# 030Card.net
KiCad netlist of a schematic drawn in EAGLE
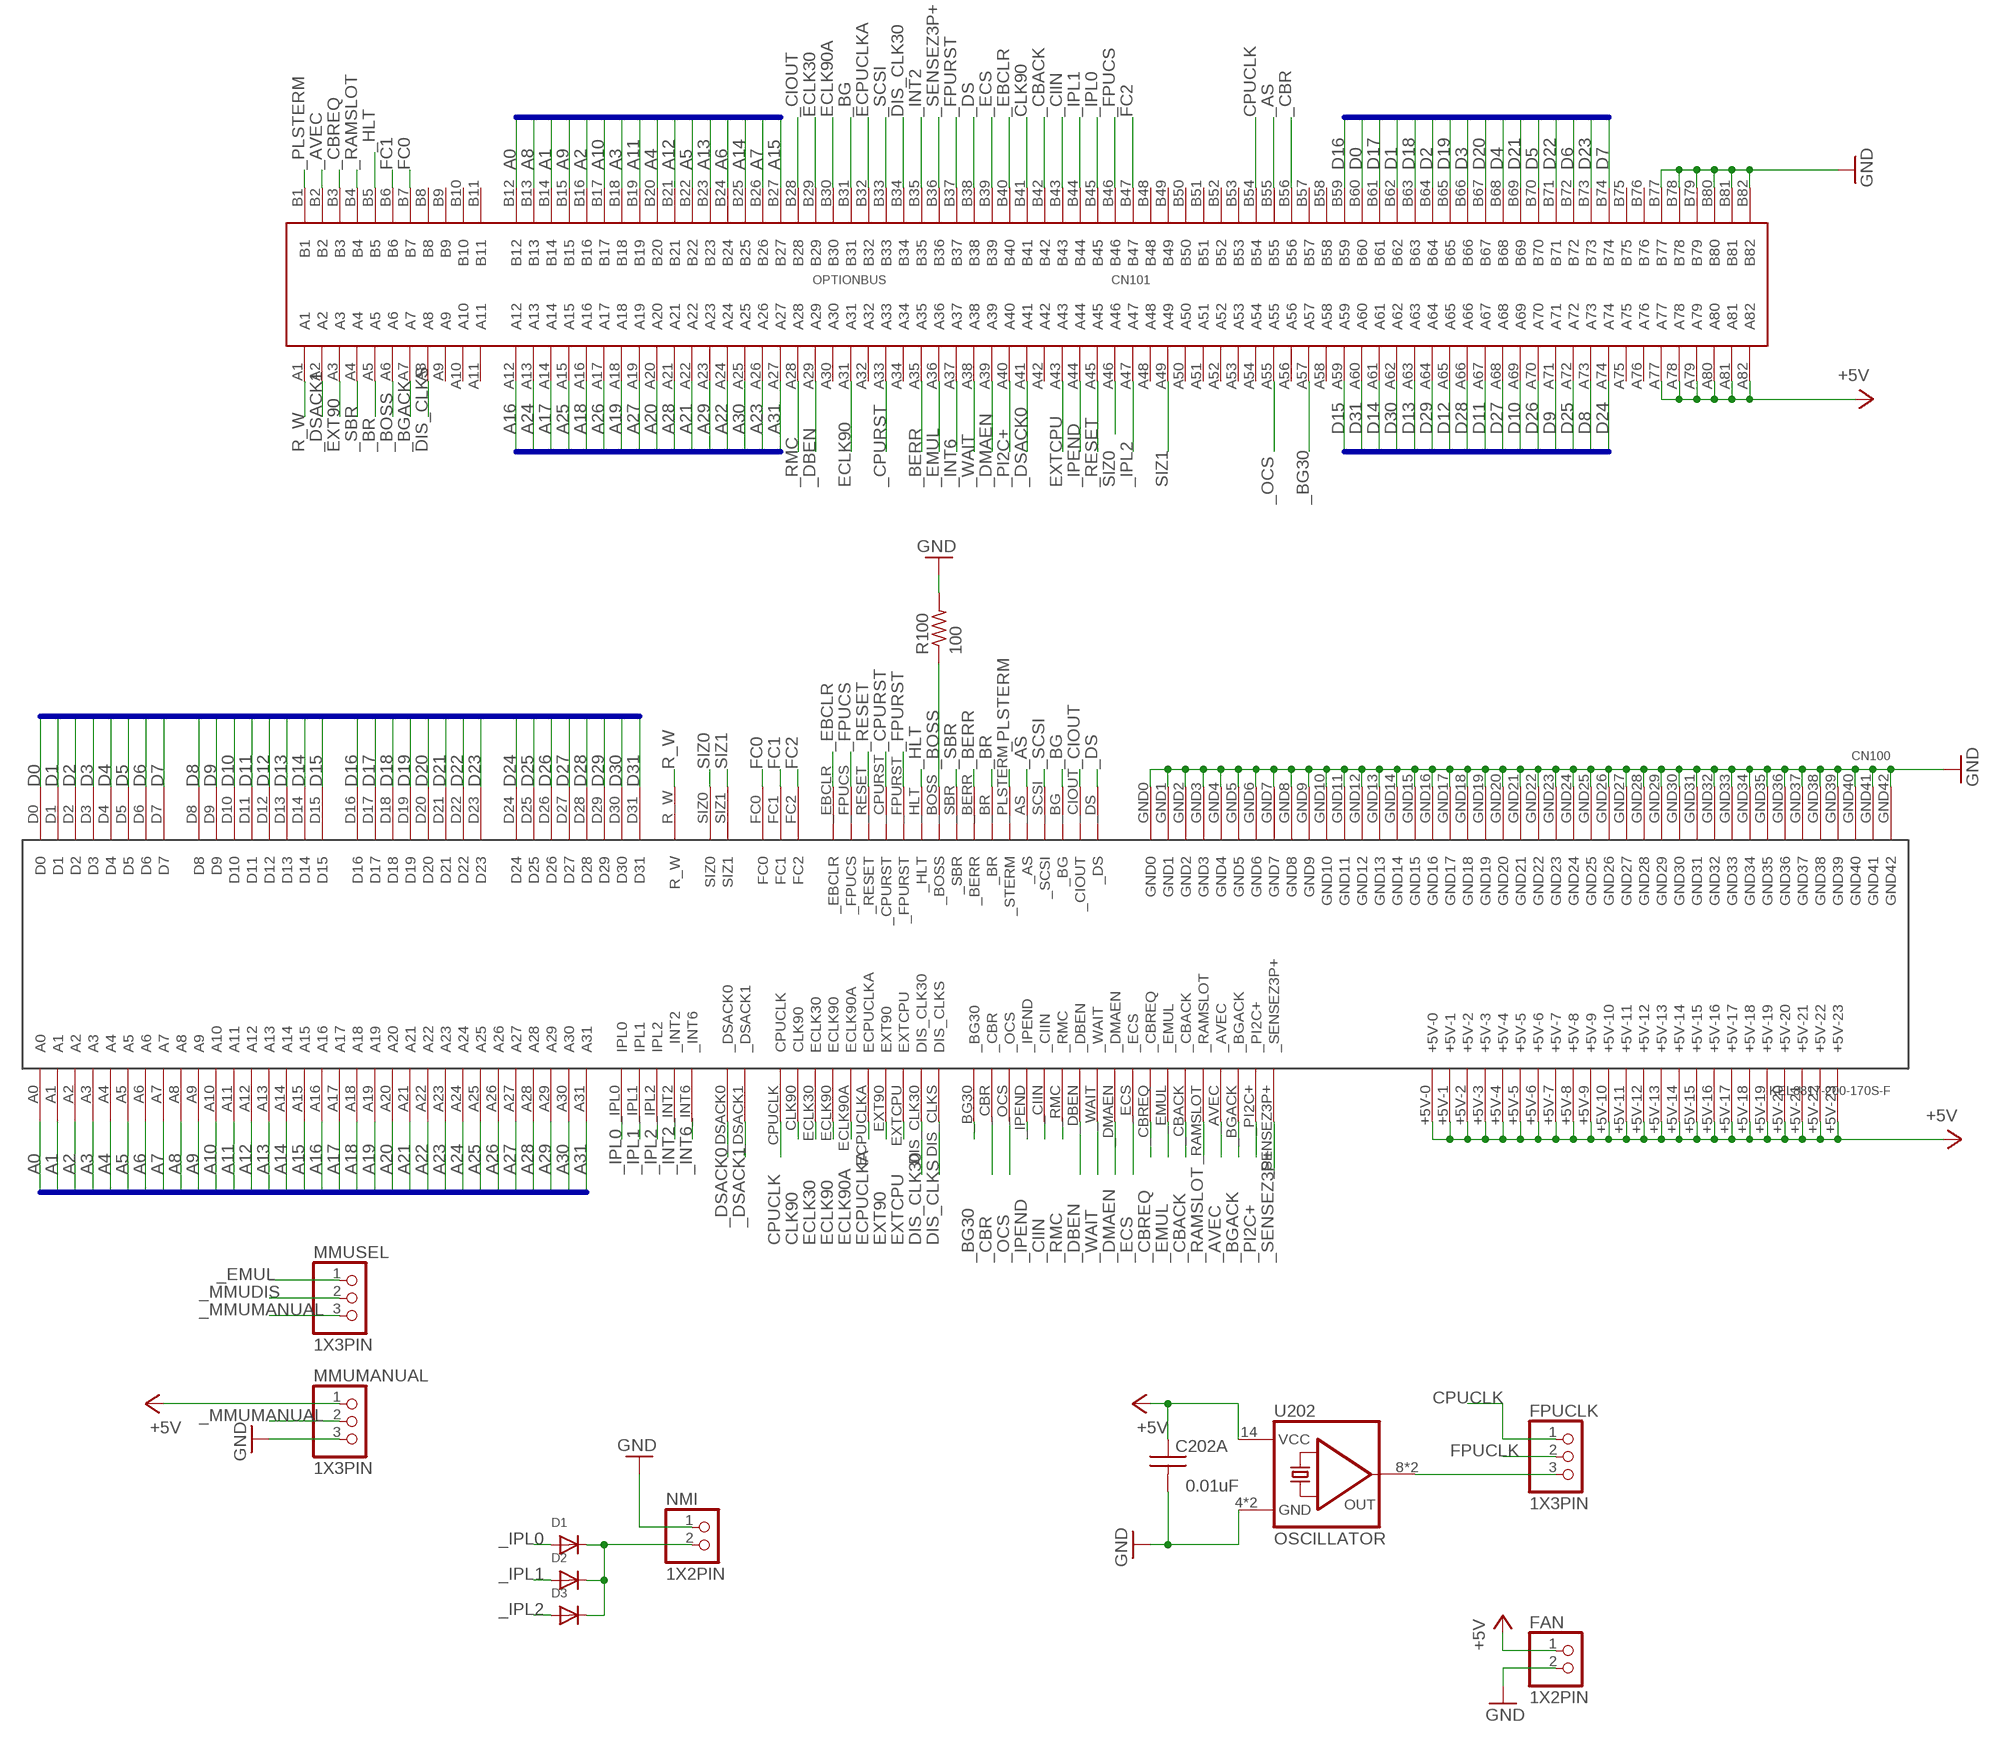
[diagram p0: schematic, sheet 1, part 1 of 2]
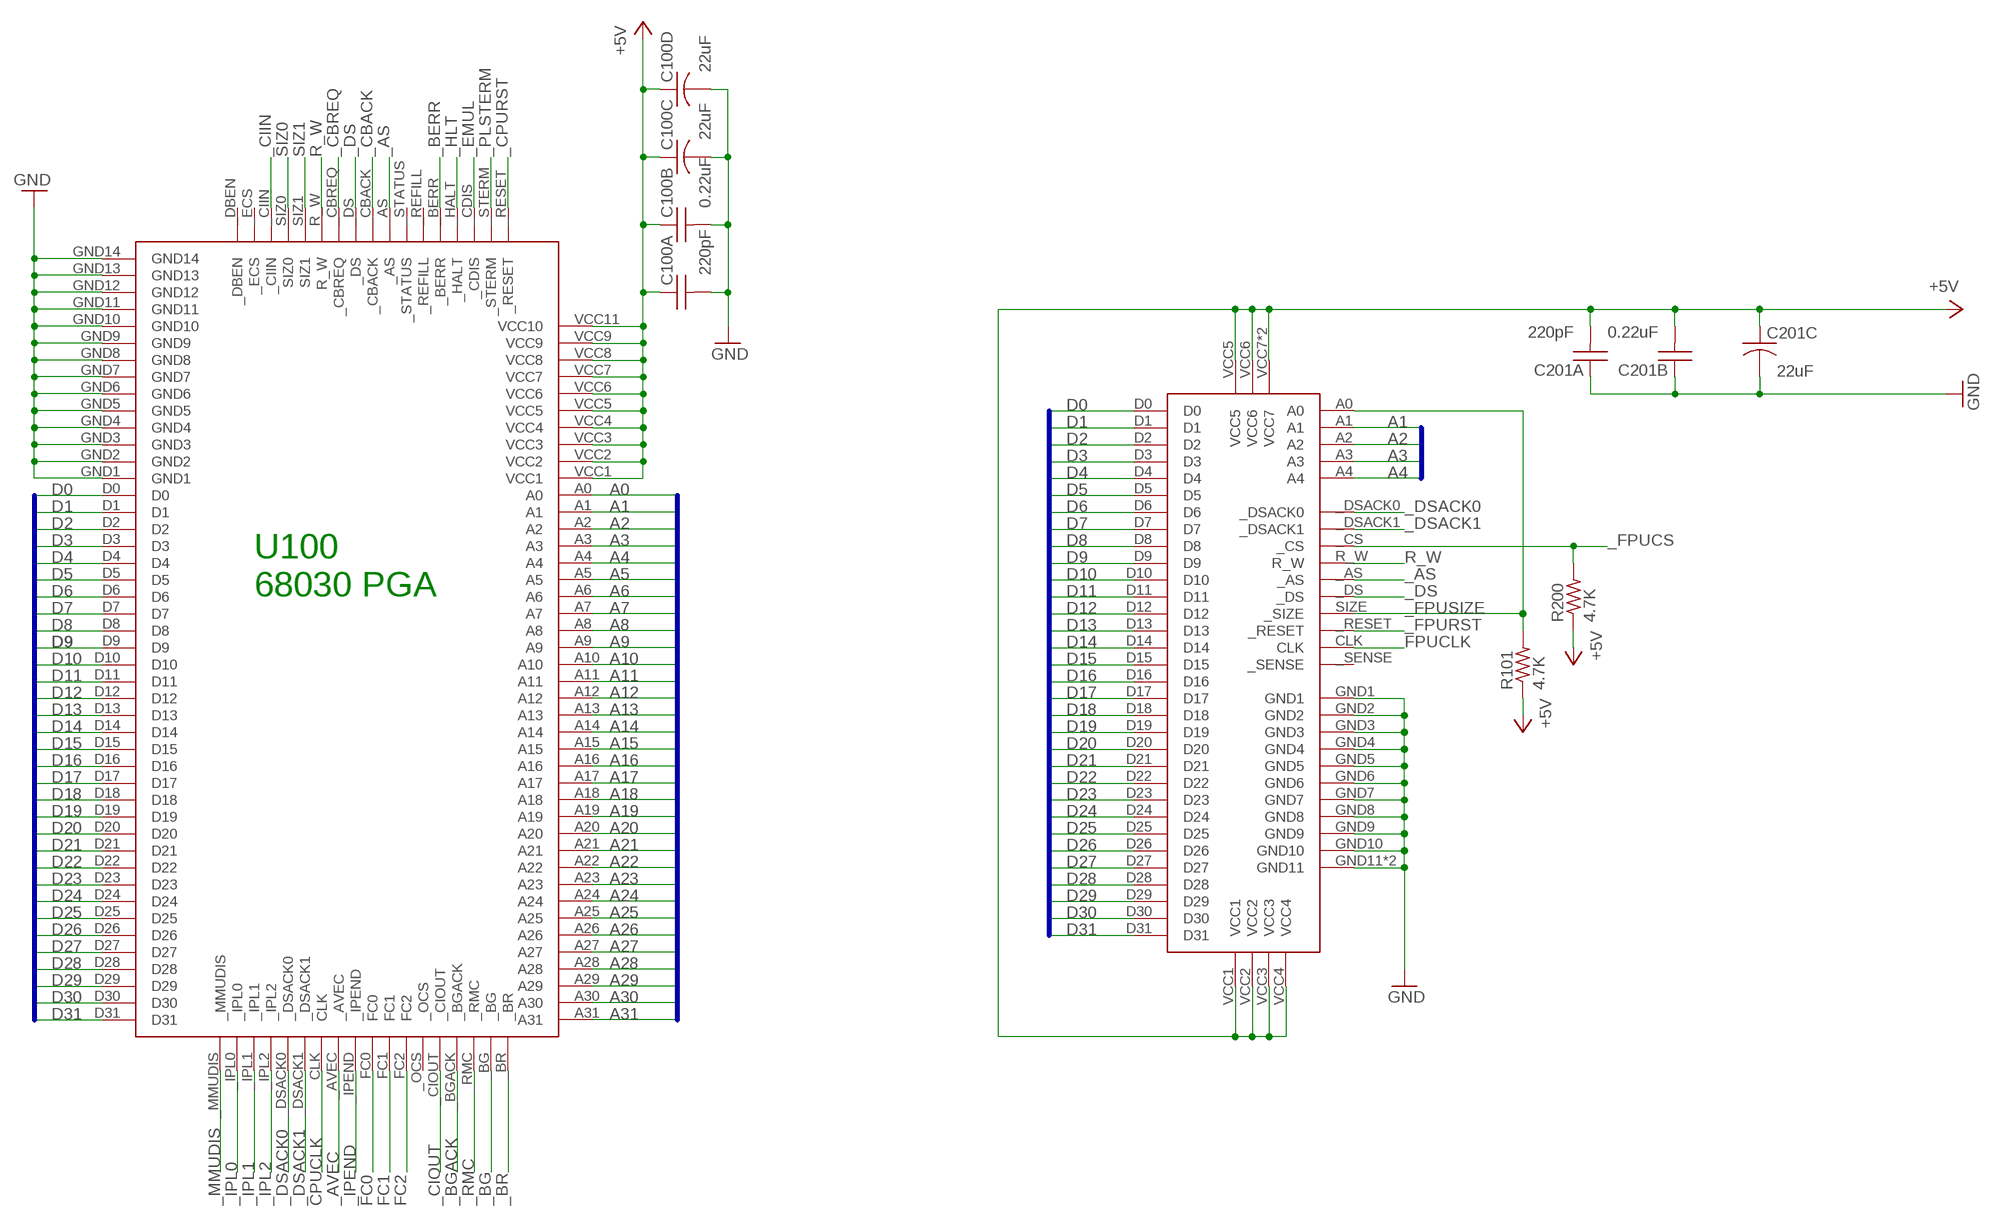
[diagram p1: schematic, sheet 1, part 2 of 2]

(export (version "E")
  (design (tool "Eeschema 10.0.6"))
  (components
    (comp (ref "C100A")
      (value "220pF")
      (footprint "eagle-import:R0805")
      (libsource (lib "eagle-import") (part "C0805"))
    )
    (comp (ref "C100B")
      (value "0.22uF")
      (footprint "eagle-import:R0805")
      (libsource (lib "eagle-import") (part "C0805"))
    )
    (comp (ref "C100C")
      (value "22uF")
      (footprint "eagle-import:SMD-ELECTROLYTE")
      (libsource (lib "eagle-import") (part "SMD-ELECTROLYTE"))
    )
    (comp (ref "C100D")
      (value "22uF")
      (footprint "eagle-import:SMD-ELECTROLYTE")
      (libsource (lib "eagle-import") (part "SMD-ELECTROLYTE"))
    )
    (comp (ref "C201A")
      (value "220pF")
      (footprint "eagle-import:R0805")
      (libsource (lib "eagle-import") (part "C0805"))
    )
    (comp (ref "C201B")
      (value "0.22uF")
      (footprint "eagle-import:R0805")
      (libsource (lib "eagle-import") (part "C0805"))
    )
    (comp (ref "C201C")
      (value "22uF")
      (footprint "eagle-import:SMD-ELECTROLYTE")
      (libsource (lib "eagle-import") (part "SMD-ELECTROLYTE"))
    )
    (comp (ref "C202A")
      (value "0.01uF")
      (footprint "eagle-import:R0805")
      (libsource (lib "eagle-import") (part "C0805"))
    )
    (comp (ref "CN100")
      (value "KEL8817-200-170S-F")
      (footprint "eagle-import:KEL8817-200-170S-F")
      (libsource (lib "eagle-import") (part "KEL8817-200-170S-F"))
    )
    (comp (ref "CN101")
      (value "OPTIONBUS")
      (footprint "eagle-import:OPTIONBUS")
      (libsource (lib "eagle-import") (part "OPTIONBUS"))
    )
    (comp (ref "D1")
      (value "DIODESOD-323F")
      (footprint "eagle-import:SOD-323F")
      (libsource (lib "eagle-import") (part "DIODESOD-323F"))
    )
    (comp (ref "D2")
      (value "DIODESOD-323F")
      (footprint "eagle-import:SOD-323F")
      (libsource (lib "eagle-import") (part "DIODESOD-323F"))
    )
    (comp (ref "D3")
      (value "DIODESOD-323F")
      (footprint "eagle-import:SOD-323F")
      (libsource (lib "eagle-import") (part "DIODESOD-323F"))
    )
    (comp (ref "FAN")
      (value "1X2PIN")
      (footprint "eagle-import:1X2PIN")
      (libsource (lib "eagle-import") (part "1X2PIN"))
    )
    (comp (ref "FPUCLK")
      (value "1X3PIN")
      (footprint "eagle-import:1X3PIN")
      (libsource (lib "eagle-import") (part "1X3PIN"))
    )
    (comp (ref "MMUMANUAL")
      (value "1X3PIN")
      (footprint "eagle-import:1X3PIN")
      (libsource (lib "eagle-import") (part "1X3PIN"))
    )
    (comp (ref "MMUSEL")
      (value "1X3PIN")
      (footprint "eagle-import:1X3PIN")
      (libsource (lib "eagle-import") (part "1X3PIN"))
    )
    (comp (ref "NMI")
      (value "1X2PIN")
      (footprint "eagle-import:1X2PIN")
      (libsource (lib "eagle-import") (part "1X2PIN"))
    )
    (comp (ref "R100")
      (value "100")
      (footprint "eagle-import:R0805")
      (libsource (lib "eagle-import") (part "R-US_R0805"))
    )
    (comp (ref "R101")
      (value "4.7K")
      (footprint "eagle-import:R0805")
      (libsource (lib "eagle-import") (part "R-US_R0805"))
    )
    (comp (ref "R200")
      (value "4.7K")
      (footprint "eagle-import:R0805")
      (libsource (lib "eagle-import") (part "R-US_R0805"))
    )
    (comp (ref "U100")
      (value "M68030")
      (footprint "eagle-import:M68030")
      (libsource (lib "eagle-import") (part "M68030"))
    )
    (comp (ref "U201")
      (value "M68882PLCC")
      (footprint "eagle-import:M68882PLCC")
      (libsource (lib "eagle-import") (part "M68882PLCC"))
    )
    (comp (ref "U202")
      (value "OSCILLATOR")
      (footprint "eagle-import:OSCILLATOR")
      (libsource (lib "eagle-import") (part "OSCILLATOR"))
    )
  )
  (nets
    (net (code "1") (name "+5V") (class "Default")
      (node (ref "C100A") (pin "1") (pinfunction "1_1") (pintype "passive"))
      (node (ref "C100B") (pin "1") (pinfunction "1_1") (pintype "passive"))
      (node (ref "C100C") (pin "+") (pinfunction "1_+") (pintype "passive"))
      (node (ref "C100D") (pin "+") (pinfunction "1_+") (pintype "passive"))
      (node (ref "C201A") (pin "2") (pinfunction "2_2") (pintype "passive"))
      (node (ref "C201B") (pin "2") (pinfunction "2_2") (pintype "passive"))
      (node (ref "C201C") (pin "+") (pinfunction "1_+") (pintype "passive"))
      (node (ref "C202A") (pin "1") (pinfunction "1_1") (pintype "passive"))
      (node (ref "CN100") (pin "+5V-0") (pinfunction "+5V-0_+5V-0") (pintype "bidirectional"))
      (node (ref "CN100") (pin "+5V-1") (pinfunction "+5V-1_+5V-1") (pintype "bidirectional"))
      (node (ref "CN100") (pin "+5V-10") (pinfunction "+5V-10_+5V-10") (pintype "bidirectional"))
      (node (ref "CN100") (pin "+5V-11") (pinfunction "+5V-11_+5V-11") (pintype "bidirectional"))
      (node (ref "CN100") (pin "+5V-12") (pinfunction "+5V-12_+5V-12") (pintype "bidirectional"))
      (node (ref "CN100") (pin "+5V-13") (pinfunction "+5V-13_+5V-13") (pintype "bidirectional"))
      (node (ref "CN100") (pin "+5V-14") (pinfunction "+5V-14_+5V-14") (pintype "bidirectional"))
      (node (ref "CN100") (pin "+5V-15") (pinfunction "+5V-15_+5V-15") (pintype "bidirectional"))
      (node (ref "CN100") (pin "+5V-16") (pinfunction "+5V-16_+5V-16") (pintype "bidirectional"))
      (node (ref "CN100") (pin "+5V-17") (pinfunction "+5V-17_+5V-17") (pintype "bidirectional"))
      (node (ref "CN100") (pin "+5V-18") (pinfunction "+5V-18_+5V-18") (pintype "bidirectional"))
      (node (ref "CN100") (pin "+5V-19") (pinfunction "+5V-19_+5V-19") (pintype "bidirectional"))
      (node (ref "CN100") (pin "+5V-2") (pinfunction "+5V-2_+5V-2") (pintype "bidirectional"))
      (node (ref "CN100") (pin "+5V-20") (pinfunction "+5V-20_+5V-20") (pintype "bidirectional"))
      (node (ref "CN100") (pin "+5V-21") (pinfunction "+5V-21_+5V-21") (pintype "bidirectional"))
      (node (ref "CN100") (pin "+5V-22") (pinfunction "+5V-22_+5V-22") (pintype "bidirectional"))
      (node (ref "CN100") (pin "+5V-23") (pinfunction "+5V-23_+5V-23") (pintype "bidirectional"))
      (node (ref "CN100") (pin "+5V-3") (pinfunction "+5V-3_+5V-3") (pintype "bidirectional"))
      (node (ref "CN100") (pin "+5V-4") (pinfunction "+5V-4_+5V-4") (pintype "bidirectional"))
      (node (ref "CN100") (pin "+5V-5") (pinfunction "+5V-5_+5V-5") (pintype "bidirectional"))
      (node (ref "CN100") (pin "+5V-6") (pinfunction "+5V-6_+5V-6") (pintype "bidirectional"))
      (node (ref "CN100") (pin "+5V-7") (pinfunction "+5V-7_+5V-7") (pintype "bidirectional"))
      (node (ref "CN100") (pin "+5V-8") (pinfunction "+5V-8_+5V-8") (pintype "bidirectional"))
      (node (ref "CN100") (pin "+5V-9") (pinfunction "+5V-9_+5V-9") (pintype "bidirectional"))
      (node (ref "CN101") (pin "A77") (pinfunction "A77_A77") (pintype "bidirectional"))
      (node (ref "CN101") (pin "A78") (pinfunction "A78_A78") (pintype "bidirectional"))
      (node (ref "CN101") (pin "A79") (pinfunction "A79_A79") (pintype "bidirectional"))
      (node (ref "CN101") (pin "A80") (pinfunction "A80_A80") (pintype "bidirectional"))
      (node (ref "CN101") (pin "A81") (pinfunction "A81_A81") (pintype "bidirectional"))
      (node (ref "CN101") (pin "A82") (pinfunction "A82_A82") (pintype "bidirectional"))
      (node (ref "FAN") (pin "1") (pinfunction "1_1") (pintype "passive"))
      (node (ref "MMUMANUAL") (pin "1") (pinfunction "1_1") (pintype "passive"))
      (node (ref "R101") (pin "1") (pinfunction "1_1") (pintype "passive"))
      (node (ref "R200") (pin "1") (pinfunction "1_1") (pintype "passive"))
      (node (ref "U100") (pin "VCC1") (pinfunction "VCC1_VCC1") (pintype "bidirectional"))
      (node (ref "U100") (pin "VCC11") (pinfunction "VCC10_VCC11") (pintype "bidirectional"))
      (node (ref "U100") (pin "VCC2") (pinfunction "VCC2_VCC2") (pintype "bidirectional"))
      (node (ref "U100") (pin "VCC3") (pinfunction "VCC3_VCC3") (pintype "bidirectional"))
      (node (ref "U100") (pin "VCC4") (pinfunction "VCC4_VCC4") (pintype "bidirectional"))
      (node (ref "U100") (pin "VCC5") (pinfunction "VCC5_VCC5") (pintype "bidirectional"))
      (node (ref "U100") (pin "VCC6") (pinfunction "VCC6_VCC6") (pintype "bidirectional"))
      (node (ref "U100") (pin "VCC7") (pinfunction "VCC7_VCC7") (pintype "bidirectional"))
      (node (ref "U100") (pin "VCC8") (pinfunction "VCC8_VCC8") (pintype "bidirectional"))
      (node (ref "U100") (pin "VCC9") (pinfunction "VCC9_VCC9") (pintype "bidirectional"))
      (node (ref "U201") (pin "VCC1") (pinfunction "VCC1_VCC1") (pintype "bidirectional"))
      (node (ref "U201") (pin "VCC2") (pinfunction "VCC2_VCC2") (pintype "bidirectional"))
      (node (ref "U201") (pin "VCC3") (pinfunction "VCC3_VCC3") (pintype "bidirectional"))
      (node (ref "U201") (pin "VCC4") (pinfunction "VCC4_VCC4") (pintype "bidirectional"))
      (node (ref "U201") (pin "VCC5") (pinfunction "VCC5_VCC5") (pintype "bidirectional"))
      (node (ref "U201") (pin "VCC6") (pinfunction "VCC6_VCC6") (pintype "bidirectional"))
      (node (ref "U201") (pin "VCC7") (pinfunction "VCC7_VCC7") (pintype "bidirectional"))
      (node (ref "U201") (pin "VCC8") (pinfunction "VCC7_VCC8") (pintype "bidirectional"))
      (node (ref "U202") (pin "14") (pinfunction "+5V_14") (pintype "power_in"))
    )
    (net (code "2") (name "/A0") (class "Default")
      (node (ref "CN100") (pin "A0") (pinfunction "A0_A0") (pintype "bidirectional"))
      (node (ref "CN101") (pin "B12") (pinfunction "B12_B12") (pintype "bidirectional"))
      (node (ref "U100") (pin "A0") (pinfunction "A0_A0") (pintype "bidirectional"))
    )
    (net (code "3") (name "/A1") (class "Default")
      (node (ref "CN100") (pin "A1") (pinfunction "A1_A1") (pintype "bidirectional"))
      (node (ref "CN101") (pin "B14") (pinfunction "B14_B14") (pintype "bidirectional"))
      (node (ref "U100") (pin "A1") (pinfunction "A1_A1") (pintype "bidirectional"))
      (node (ref "U201") (pin "A1") (pinfunction "A1_A1") (pintype "bidirectional"))
    )
    (net (code "4") (name "/A2") (class "Default")
      (node (ref "CN100") (pin "A2") (pinfunction "A2_A2") (pintype "bidirectional"))
      (node (ref "CN101") (pin "B16") (pinfunction "B16_B16") (pintype "bidirectional"))
      (node (ref "U100") (pin "A2") (pinfunction "A2_A2") (pintype "bidirectional"))
      (node (ref "U201") (pin "A2") (pinfunction "A2_A2") (pintype "bidirectional"))
    )
    (net (code "5") (name "/A3") (class "Default")
      (node (ref "CN100") (pin "A3") (pinfunction "A3_A3") (pintype "bidirectional"))
      (node (ref "CN101") (pin "B18") (pinfunction "B18_B18") (pintype "bidirectional"))
      (node (ref "U100") (pin "A3") (pinfunction "A3_A3") (pintype "bidirectional"))
      (node (ref "U201") (pin "A3") (pinfunction "A3_A3") (pintype "bidirectional"))
    )
    (net (code "6") (name "/A4") (class "Default")
      (node (ref "CN100") (pin "A4") (pinfunction "A4_A4") (pintype "bidirectional"))
      (node (ref "CN101") (pin "B20") (pinfunction "B20_B20") (pintype "bidirectional"))
      (node (ref "U100") (pin "A4") (pinfunction "A4_A4") (pintype "bidirectional"))
      (node (ref "U201") (pin "A4") (pinfunction "A4_A4") (pintype "bidirectional"))
    )
    (net (code "7") (name "/A5") (class "Default")
      (node (ref "CN100") (pin "A5") (pinfunction "A5_A5") (pintype "bidirectional"))
      (node (ref "CN101") (pin "B22") (pinfunction "B22_B22") (pintype "bidirectional"))
      (node (ref "U100") (pin "A5") (pinfunction "A5_A5") (pintype "bidirectional"))
    )
    (net (code "8") (name "/A6") (class "Default")
      (node (ref "CN100") (pin "A6") (pinfunction "A6_A6") (pintype "bidirectional"))
      (node (ref "CN101") (pin "B24") (pinfunction "B24_B24") (pintype "bidirectional"))
      (node (ref "U100") (pin "A6") (pinfunction "A6_A6") (pintype "bidirectional"))
    )
    (net (code "9") (name "/A7") (class "Default")
      (node (ref "CN100") (pin "A7") (pinfunction "A7_A7") (pintype "bidirectional"))
      (node (ref "CN101") (pin "B26") (pinfunction "B26_B26") (pintype "bidirectional"))
      (node (ref "U100") (pin "A7") (pinfunction "A7_A7") (pintype "bidirectional"))
    )
    (net (code "10") (name "/A8") (class "Default")
      (node (ref "CN100") (pin "A8") (pinfunction "A8_A8") (pintype "bidirectional"))
      (node (ref "CN101") (pin "B13") (pinfunction "B13_B13") (pintype "bidirectional"))
      (node (ref "U100") (pin "A8") (pinfunction "A8_A8") (pintype "bidirectional"))
    )
    (net (code "11") (name "/A9") (class "Default")
      (node (ref "CN100") (pin "A9") (pinfunction "A9_A9") (pintype "bidirectional"))
      (node (ref "CN101") (pin "B15") (pinfunction "B15_B15") (pintype "bidirectional"))
      (node (ref "U100") (pin "A9") (pinfunction "A9_A9") (pintype "bidirectional"))
    )
    (net (code "12") (name "/A10") (class "Default")
      (node (ref "CN100") (pin "A10") (pinfunction "A10_A10") (pintype "bidirectional"))
      (node (ref "CN101") (pin "B17") (pinfunction "B17_B17") (pintype "bidirectional"))
      (node (ref "U100") (pin "A10") (pinfunction "A10_A10") (pintype "bidirectional"))
    )
    (net (code "13") (name "/A11") (class "Default")
      (node (ref "CN100") (pin "A11") (pinfunction "A11_A11") (pintype "bidirectional"))
      (node (ref "CN101") (pin "B19") (pinfunction "B19_B19") (pintype "bidirectional"))
      (node (ref "U100") (pin "A11") (pinfunction "A11_A11") (pintype "bidirectional"))
    )
    (net (code "14") (name "/A12") (class "Default")
      (node (ref "CN100") (pin "A12") (pinfunction "A12_A12") (pintype "bidirectional"))
      (node (ref "CN101") (pin "B21") (pinfunction "B21_B21") (pintype "bidirectional"))
      (node (ref "U100") (pin "A12") (pinfunction "A12_A12") (pintype "bidirectional"))
    )
    (net (code "15") (name "/A13") (class "Default")
      (node (ref "CN100") (pin "A13") (pinfunction "A13_A13") (pintype "bidirectional"))
      (node (ref "CN101") (pin "B23") (pinfunction "B23_B23") (pintype "bidirectional"))
      (node (ref "U100") (pin "A13") (pinfunction "A13_A13") (pintype "bidirectional"))
    )
    (net (code "16") (name "/A14") (class "Default")
      (node (ref "CN100") (pin "A14") (pinfunction "A14_A14") (pintype "bidirectional"))
      (node (ref "CN101") (pin "B25") (pinfunction "B25_B25") (pintype "bidirectional"))
      (node (ref "U100") (pin "A14") (pinfunction "A14_A14") (pintype "bidirectional"))
    )
    (net (code "17") (name "/A15") (class "Default")
      (node (ref "CN100") (pin "A15") (pinfunction "A15_A15") (pintype "bidirectional"))
      (node (ref "CN101") (pin "B27") (pinfunction "B27_B27") (pintype "bidirectional"))
      (node (ref "U100") (pin "A15") (pinfunction "A15_A15") (pintype "bidirectional"))
    )
    (net (code "18") (name "/A16") (class "Default")
      (node (ref "CN100") (pin "A16") (pinfunction "A16_A16") (pintype "bidirectional"))
      (node (ref "CN101") (pin "A12") (pinfunction "A12_A12") (pintype "bidirectional"))
      (node (ref "U100") (pin "A16") (pinfunction "A16_A16") (pintype "bidirectional"))
    )
    (net (code "19") (name "/A17") (class "Default")
      (node (ref "CN100") (pin "A17") (pinfunction "A17_A17") (pintype "bidirectional"))
      (node (ref "CN101") (pin "A14") (pinfunction "A14_A14") (pintype "bidirectional"))
      (node (ref "U100") (pin "A17") (pinfunction "A17_A17") (pintype "bidirectional"))
    )
    (net (code "20") (name "/A18") (class "Default")
      (node (ref "CN100") (pin "A18") (pinfunction "A18_A18") (pintype "bidirectional"))
      (node (ref "CN101") (pin "A16") (pinfunction "A16_A16") (pintype "bidirectional"))
      (node (ref "U100") (pin "A18") (pinfunction "A18_A18") (pintype "bidirectional"))
    )
    (net (code "21") (name "/A19") (class "Default")
      (node (ref "CN100") (pin "A19") (pinfunction "A19_A19") (pintype "bidirectional"))
      (node (ref "CN101") (pin "A18") (pinfunction "A18_A18") (pintype "bidirectional"))
      (node (ref "U100") (pin "A19") (pinfunction "A19_A19") (pintype "bidirectional"))
    )
    (net (code "22") (name "/A20") (class "Default")
      (node (ref "CN100") (pin "A20") (pinfunction "A20_A20") (pintype "bidirectional"))
      (node (ref "CN101") (pin "A20") (pinfunction "A20_A20") (pintype "bidirectional"))
      (node (ref "U100") (pin "A20") (pinfunction "A20_A20") (pintype "bidirectional"))
    )
    (net (code "23") (name "/A21") (class "Default")
      (node (ref "CN100") (pin "A21") (pinfunction "A21_A21") (pintype "bidirectional"))
      (node (ref "CN101") (pin "A22") (pinfunction "A22_A22") (pintype "bidirectional"))
      (node (ref "U100") (pin "A21") (pinfunction "A21_A21") (pintype "bidirectional"))
    )
    (net (code "24") (name "/A22") (class "Default")
      (node (ref "CN100") (pin "A22") (pinfunction "A22_A22") (pintype "bidirectional"))
      (node (ref "CN101") (pin "A24") (pinfunction "A24_A24") (pintype "bidirectional"))
      (node (ref "U100") (pin "A22") (pinfunction "A22_A22") (pintype "bidirectional"))
    )
    (net (code "25") (name "/A23") (class "Default")
      (node (ref "CN100") (pin "A23") (pinfunction "A23_A23") (pintype "bidirectional"))
      (node (ref "CN101") (pin "A26") (pinfunction "A26_A26") (pintype "bidirectional"))
      (node (ref "U100") (pin "A23") (pinfunction "A23_A23") (pintype "bidirectional"))
    )
    (net (code "26") (name "/A24") (class "Default")
      (node (ref "CN100") (pin "A24") (pinfunction "A24_A24") (pintype "bidirectional"))
      (node (ref "CN101") (pin "A13") (pinfunction "A13_A13") (pintype "bidirectional"))
      (node (ref "U100") (pin "A24") (pinfunction "A24_A24") (pintype "bidirectional"))
    )
    (net (code "27") (name "/A25") (class "Default")
      (node (ref "CN100") (pin "A25") (pinfunction "A25_A25") (pintype "bidirectional"))
      (node (ref "CN101") (pin "A15") (pinfunction "A15_A15") (pintype "bidirectional"))
      (node (ref "U100") (pin "A25") (pinfunction "A25_A25") (pintype "bidirectional"))
    )
    (net (code "28") (name "/A26") (class "Default")
      (node (ref "CN100") (pin "A26") (pinfunction "A26_A26") (pintype "bidirectional"))
      (node (ref "CN101") (pin "A17") (pinfunction "A17_A17") (pintype "bidirectional"))
      (node (ref "U100") (pin "A26") (pinfunction "A26_A26") (pintype "bidirectional"))
    )
    (net (code "29") (name "/A27") (class "Default")
      (node (ref "CN100") (pin "A27") (pinfunction "A27_A27") (pintype "bidirectional"))
      (node (ref "CN101") (pin "A19") (pinfunction "A19_A19") (pintype "bidirectional"))
      (node (ref "U100") (pin "A27") (pinfunction "A27_A27") (pintype "bidirectional"))
    )
    (net (code "30") (name "/A28") (class "Default")
      (node (ref "CN100") (pin "A28") (pinfunction "A28_A28") (pintype "bidirectional"))
      (node (ref "CN101") (pin "A21") (pinfunction "A21_A21") (pintype "bidirectional"))
      (node (ref "U100") (pin "A28") (pinfunction "A28_A28") (pintype "bidirectional"))
    )
    (net (code "31") (name "/A29") (class "Default")
      (node (ref "CN100") (pin "A29") (pinfunction "A29_A29") (pintype "bidirectional"))
      (node (ref "CN101") (pin "A23") (pinfunction "A23_A23") (pintype "bidirectional"))
      (node (ref "U100") (pin "A29") (pinfunction "A29_A29") (pintype "bidirectional"))
    )
    (net (code "32") (name "/A30") (class "Default")
      (node (ref "CN100") (pin "A30") (pinfunction "A30_A30") (pintype "bidirectional"))
      (node (ref "CN101") (pin "A25") (pinfunction "A25_A25") (pintype "bidirectional"))
      (node (ref "U100") (pin "A30") (pinfunction "A30_A30") (pintype "bidirectional"))
    )
    (net (code "33") (name "/A31") (class "Default")
      (node (ref "CN100") (pin "A31") (pinfunction "A31_A31") (pintype "bidirectional"))
      (node (ref "CN101") (pin "A27") (pinfunction "A27_A27") (pintype "bidirectional"))
      (node (ref "U100") (pin "A31") (pinfunction "A31_A31") (pintype "bidirectional"))
    )
    (net (code "34") (name "/CLK90") (class "Default")
      (node (ref "CN100") (pin "CLK90") (pinfunction "CLK90_CLK90") (pintype "bidirectional"))
      (node (ref "CN101") (pin "B41") (pinfunction "B41_B41") (pintype "bidirectional"))
    )
    (net (code "35") (name "/CPUCLK") (class "Default")
      (node (ref "CN100") (pin "CPUCLK") (pinfunction "CPUCLK_CPUCLK") (pintype "bidirectional"))
      (node (ref "CN101") (pin "B54") (pinfunction "B54_B54") (pintype "bidirectional"))
      (node (ref "FPUCLK") (pin "1") (pinfunction "1_1") (pintype "passive"))
      (node (ref "U100") (pin "CLK") (pinfunction "CLK_CLK") (pintype "bidirectional"))
    )
    (net (code "36") (name "/D0") (class "Default")
      (node (ref "CN100") (pin "D0") (pinfunction "D0_D0") (pintype "bidirectional"))
      (node (ref "CN101") (pin "B60") (pinfunction "B60_B60") (pintype "bidirectional"))
      (node (ref "U100") (pin "D0") (pinfunction "D0_D0") (pintype "bidirectional"))
      (node (ref "U201") (pin "D0") (pinfunction "D0_D0") (pintype "bidirectional"))
    )
    (net (code "37") (name "/D1") (class "Default")
      (node (ref "CN100") (pin "D1") (pinfunction "D1_D1") (pintype "bidirectional"))
      (node (ref "CN101") (pin "B62") (pinfunction "B62_B62") (pintype "bidirectional"))
      (node (ref "U100") (pin "D1") (pinfunction "D1_D1") (pintype "bidirectional"))
      (node (ref "U201") (pin "D1") (pinfunction "D1_D1") (pintype "bidirectional"))
    )
    (net (code "38") (name "/D2") (class "Default")
      (node (ref "CN100") (pin "D2") (pinfunction "D2_D2") (pintype "bidirectional"))
      (node (ref "CN101") (pin "B64") (pinfunction "B64_B64") (pintype "bidirectional"))
      (node (ref "U100") (pin "D2") (pinfunction "D2_D2") (pintype "bidirectional"))
      (node (ref "U201") (pin "D2") (pinfunction "D2_D2") (pintype "bidirectional"))
    )
    (net (code "39") (name "/D3") (class "Default")
      (node (ref "CN100") (pin "D3") (pinfunction "D3_D3") (pintype "bidirectional"))
      (node (ref "CN101") (pin "B66") (pinfunction "B66_B66") (pintype "bidirectional"))
      (node (ref "U100") (pin "D3") (pinfunction "D3_D3") (pintype "bidirectional"))
      (node (ref "U201") (pin "D3") (pinfunction "D3_D3") (pintype "bidirectional"))
    )
    (net (code "40") (name "/D4") (class "Default")
      (node (ref "CN100") (pin "D4") (pinfunction "D4_D4") (pintype "bidirectional"))
      (node (ref "CN101") (pin "B68") (pinfunction "B68_B68") (pintype "bidirectional"))
      (node (ref "U100") (pin "D4") (pinfunction "D4_D4") (pintype "bidirectional"))
      (node (ref "U201") (pin "D4") (pinfunction "D4_D4") (pintype "bidirectional"))
    )
    (net (code "41") (name "/D5") (class "Default")
      (node (ref "CN100") (pin "D5") (pinfunction "D5_D5") (pintype "bidirectional"))
      (node (ref "CN101") (pin "B70") (pinfunction "B70_B70") (pintype "bidirectional"))
      (node (ref "U100") (pin "D5") (pinfunction "D5_D5") (pintype "bidirectional"))
      (node (ref "U201") (pin "D5") (pinfunction "D5_D5") (pintype "bidirectional"))
    )
    (net (code "42") (name "/D6") (class "Default")
      (node (ref "CN100") (pin "D6") (pinfunction "D6_D6") (pintype "bidirectional"))
      (node (ref "CN101") (pin "B72") (pinfunction "B72_B72") (pintype "bidirectional"))
      (node (ref "U100") (pin "D6") (pinfunction "D6_D6") (pintype "bidirectional"))
      (node (ref "U201") (pin "D6") (pinfunction "D6_D6") (pintype "bidirectional"))
    )
    (net (code "43") (name "/D7") (class "Default")
      (node (ref "CN100") (pin "D7") (pinfunction "D7_D7") (pintype "bidirectional"))
      (node (ref "CN101") (pin "B74") (pinfunction "B74_B74") (pintype "bidirectional"))
      (node (ref "U100") (pin "D7") (pinfunction "D7_D7") (pintype "bidirectional"))
      (node (ref "U201") (pin "D7") (pinfunction "D7_D7") (pintype "bidirectional"))
    )
    (net (code "44") (name "/D8") (class "Default")
      (node (ref "CN100") (pin "D8") (pinfunction "D8_D8") (pintype "bidirectional"))
      (node (ref "CN101") (pin "A73") (pinfunction "A73_A73") (pintype "bidirectional"))
      (node (ref "U100") (pin "D8") (pinfunction "D8_D8") (pintype "bidirectional"))
      (node (ref "U201") (pin "D8") (pinfunction "D8_D8") (pintype "bidirectional"))
    )
    (net (code "45") (name "/D9") (class "Default")
      (node (ref "CN100") (pin "D9") (pinfunction "D9_D9") (pintype "bidirectional"))
      (node (ref "CN101") (pin "A71") (pinfunction "A71_A71") (pintype "bidirectional"))
      (node (ref "U100") (pin "D9") (pinfunction "D9_D9") (pintype "bidirectional"))
      (node (ref "U201") (pin "D9") (pinfunction "D9_D9") (pintype "bidirectional"))
    )
    (net (code "46") (name "/D10") (class "Default")
      (node (ref "CN100") (pin "D10") (pinfunction "D10_D10") (pintype "bidirectional"))
      (node (ref "CN101") (pin "A69") (pinfunction "A69_A69") (pintype "bidirectional"))
      (node (ref "U100") (pin "D10") (pinfunction "D10_D10") (pintype "bidirectional"))
      (node (ref "U201") (pin "D10") (pinfunction "D10_D10") (pintype "bidirectional"))
    )
    (net (code "47") (name "/D11") (class "Default")
      (node (ref "CN100") (pin "D11") (pinfunction "D11_D11") (pintype "bidirectional"))
      (node (ref "CN101") (pin "A67") (pinfunction "A67_A67") (pintype "bidirectional"))
      (node (ref "U100") (pin "D11") (pinfunction "D11_D11") (pintype "bidirectional"))
      (node (ref "U201") (pin "D11") (pinfunction "D11_D11") (pintype "bidirectional"))
    )
    (net (code "48") (name "/D12") (class "Default")
      (node (ref "CN100") (pin "D12") (pinfunction "D12_D12") (pintype "bidirectional"))
      (node (ref "CN101") (pin "A65") (pinfunction "A65_A65") (pintype "bidirectional"))
      (node (ref "U100") (pin "D12") (pinfunction "D12_D12") (pintype "bidirectional"))
      (node (ref "U201") (pin "D12") (pinfunction "D12_D12") (pintype "bidirectional"))
    )
    (net (code "49") (name "/D13") (class "Default")
      (node (ref "CN100") (pin "D13") (pinfunction "D13_D13") (pintype "bidirectional"))
      (node (ref "CN101") (pin "A63") (pinfunction "A63_A63") (pintype "bidirectional"))
      (node (ref "U100") (pin "D13") (pinfunction "D13_D13") (pintype "bidirectional"))
      (node (ref "U201") (pin "D13") (pinfunction "D13_D13") (pintype "bidirectional"))
    )
    (net (code "50") (name "/D14") (class "Default")
      (node (ref "CN100") (pin "D14") (pinfunction "D14_D14") (pintype "bidirectional"))
      (node (ref "CN101") (pin "A61") (pinfunction "A61_A61") (pintype "bidirectional"))
      (node (ref "U100") (pin "D14") (pinfunction "D14_D14") (pintype "bidirectional"))
      (node (ref "U201") (pin "D14") (pinfunction "D14_D14") (pintype "bidirectional"))
    )
    (net (code "51") (name "/D15") (class "Default")
      (node (ref "CN100") (pin "D15") (pinfunction "D15_D15") (pintype "bidirectional"))
      (node (ref "CN101") (pin "A59") (pinfunction "A59_A59") (pintype "bidirectional"))
      (node (ref "U100") (pin "D15") (pinfunction "D15_D15") (pintype "bidirectional"))
      (node (ref "U201") (pin "D15") (pinfunction "D15_D15") (pintype "bidirectional"))
    )
    (net (code "52") (name "/D16") (class "Default")
      (node (ref "CN100") (pin "D16") (pinfunction "D16_D16") (pintype "bidirectional"))
      (node (ref "CN101") (pin "B59") (pinfunction "B59_B59") (pintype "bidirectional"))
      (node (ref "U100") (pin "D16") (pinfunction "D16_D16") (pintype "bidirectional"))
      (node (ref "U201") (pin "D16") (pinfunction "D16_D16") (pintype "bidirectional"))
    )
    (net (code "53") (name "/D17") (class "Default")
      (node (ref "CN100") (pin "D17") (pinfunction "D17_D17") (pintype "bidirectional"))
      (node (ref "CN101") (pin "B61") (pinfunction "B61_B61") (pintype "bidirectional"))
      (node (ref "U100") (pin "D17") (pinfunction "D17_D17") (pintype "bidirectional"))
      (node (ref "U201") (pin "D17") (pinfunction "D17_D17") (pintype "bidirectional"))
    )
    (net (code "54") (name "/D18") (class "Default")
      (node (ref "CN100") (pin "D18") (pinfunction "D18_D18") (pintype "bidirectional"))
      (node (ref "CN101") (pin "B63") (pinfunction "B63_B63") (pintype "bidirectional"))
      (node (ref "U100") (pin "D18") (pinfunction "D18_D18") (pintype "bidirectional"))
      (node (ref "U201") (pin "D18") (pinfunction "D18_D18") (pintype "bidirectional"))
    )
    (net (code "55") (name "/D19") (class "Default")
      (node (ref "CN100") (pin "D19") (pinfunction "D19_D19") (pintype "bidirectional"))
      (node (ref "CN101") (pin "B65") (pinfunction "B65_B65") (pintype "bidirectional"))
      (node (ref "U100") (pin "D19") (pinfunction "D19_D19") (pintype "bidirectional"))
      (node (ref "U201") (pin "D19") (pinfunction "D19_D19") (pintype "bidirectional"))
    )
    (net (code "56") (name "/D20") (class "Default")
      (node (ref "CN100") (pin "D20") (pinfunction "D20_D20") (pintype "bidirectional"))
      (node (ref "CN101") (pin "B67") (pinfunction "B67_B67") (pintype "bidirectional"))
      (node (ref "U100") (pin "D20") (pinfunction "D20_D20") (pintype "bidirectional"))
      (node (ref "U201") (pin "D20") (pinfunction "D20_D20") (pintype "bidirectional"))
    )
    (net (code "57") (name "/D21") (class "Default")
      (node (ref "CN100") (pin "D21") (pinfunction "D21_D21") (pintype "bidirectional"))
      (node (ref "CN101") (pin "B69") (pinfunction "B69_B69") (pintype "bidirectional"))
      (node (ref "U100") (pin "D21") (pinfunction "D21_D21") (pintype "bidirectional"))
      (node (ref "U201") (pin "D21") (pinfunction "D21_D21") (pintype "bidirectional"))
    )
    (net (code "58") (name "/D22") (class "Default")
      (node (ref "CN100") (pin "D22") (pinfunction "D22_D22") (pintype "bidirectional"))
      (node (ref "CN101") (pin "B71") (pinfunction "B71_B71") (pintype "bidirectional"))
      (node (ref "U100") (pin "D22") (pinfunction "D22_D22") (pintype "bidirectional"))
      (node (ref "U201") (pin "D22") (pinfunction "D22_D22") (pintype "bidirectional"))
    )
    (net (code "59") (name "/D23") (class "Default")
      (node (ref "CN100") (pin "D23") (pinfunction "D23_D23") (pintype "bidirectional"))
      (node (ref "CN101") (pin "B73") (pinfunction "B73_B73") (pintype "bidirectional"))
      (node (ref "U100") (pin "D23") (pinfunction "D23_D23") (pintype "bidirectional"))
      (node (ref "U201") (pin "D23") (pinfunction "D23_D23") (pintype "bidirectional"))
    )
    (net (code "60") (name "/D24") (class "Default")
      (node (ref "CN100") (pin "D24") (pinfunction "D24_D24") (pintype "bidirectional"))
      (node (ref "CN101") (pin "A74") (pinfunction "A74_A74") (pintype "bidirectional"))
      (node (ref "U100") (pin "D24") (pinfunction "D24_D24") (pintype "bidirectional"))
      (node (ref "U201") (pin "D24") (pinfunction "D24_D24") (pintype "bidirectional"))
    )
    (net (code "61") (name "/D25") (class "Default")
      (node (ref "CN100") (pin "D25") (pinfunction "D25_D25") (pintype "bidirectional"))
      (node (ref "CN101") (pin "A72") (pinfunction "A72_A72") (pintype "bidirectional"))
      (node (ref "U100") (pin "D25") (pinfunction "D25_D25") (pintype "bidirectional"))
      (node (ref "U201") (pin "D25") (pinfunction "D25_D25") (pintype "bidirectional"))
    )
    (net (code "62") (name "/D26") (class "Default")
      (node (ref "CN100") (pin "D26") (pinfunction "D26_D26") (pintype "bidirectional"))
      (node (ref "CN101") (pin "A70") (pinfunction "A70_A70") (pintype "bidirectional"))
      (node (ref "U100") (pin "D26") (pinfunction "D26_D26") (pintype "bidirectional"))
      (node (ref "U201") (pin "D26") (pinfunction "D26_D26") (pintype "bidirectional"))
    )
    (net (code "63") (name "/D27") (class "Default")
      (node (ref "CN100") (pin "D27") (pinfunction "D27_D27") (pintype "bidirectional"))
      (node (ref "CN101") (pin "A68") (pinfunction "A68_A68") (pintype "bidirectional"))
      (node (ref "U100") (pin "D27") (pinfunction "D27_D27") (pintype "bidirectional"))
      (node (ref "U201") (pin "D27") (pinfunction "D27_D27") (pintype "bidirectional"))
    )
    (net (code "64") (name "/D28") (class "Default")
      (node (ref "CN100") (pin "D28") (pinfunction "D28_D28") (pintype "bidirectional"))
      (node (ref "CN101") (pin "A66") (pinfunction "A66_A66") (pintype "bidirectional"))
      (node (ref "U100") (pin "D28") (pinfunction "D28_D28") (pintype "bidirectional"))
      (node (ref "U201") (pin "D28") (pinfunction "D28_D28") (pintype "bidirectional"))
    )
    (net (code "65") (name "/D29") (class "Default")
      (node (ref "CN100") (pin "D29") (pinfunction "D29_D29") (pintype "bidirectional"))
      (node (ref "CN101") (pin "A64") (pinfunction "A64_A64") (pintype "bidirectional"))
      (node (ref "U100") (pin "D29") (pinfunction "D29_D29") (pintype "bidirectional"))
      (node (ref "U201") (pin "D29") (pinfunction "D29_D29") (pintype "bidirectional"))
    )
    (net (code "66") (name "/D30") (class "Default")
      (node (ref "CN100") (pin "D30") (pinfunction "D30_D30") (pintype "bidirectional"))
      (node (ref "CN101") (pin "A62") (pinfunction "A62_A62") (pintype "bidirectional"))
      (node (ref "U100") (pin "D30") (pinfunction "D30_D30") (pintype "bidirectional"))
      (node (ref "U201") (pin "D30") (pinfunction "D30_D30") (pintype "bidirectional"))
    )
    (net (code "67") (name "/D31") (class "Default")
      (node (ref "CN100") (pin "D31") (pinfunction "D31_D31") (pintype "bidirectional"))
      (node (ref "CN101") (pin "A60") (pinfunction "A60_A60") (pintype "bidirectional"))
      (node (ref "U100") (pin "D31") (pinfunction "D31_D31") (pintype "bidirectional"))
      (node (ref "U201") (pin "D31") (pinfunction "D31_D31") (pintype "bidirectional"))
    )
    (net (code "68") (name "/DIS_CLK30") (class "Default")
      (node (ref "CN100") (pin "DIS_CLK30") (pinfunction "DIS_CLK30_DIS_CLK30") (pintype "bidirectional"))
      (node (ref "CN101") (pin "B34") (pinfunction "B34_B34") (pintype "bidirectional"))
    )
    (net (code "69") (name "/DIS_CLKS") (class "Default")
      (node (ref "CN100") (pin "DIS_CLKS") (pinfunction "DIS_CLKS_DIS_CLKS") (pintype "bidirectional"))
      (node (ref "CN101") (pin "A8") (pinfunction "A8_A8") (pintype "bidirectional"))
    )
    (net (code "70") (name "/ECLK30") (class "Default")
      (node (ref "CN100") (pin "ECLK30") (pinfunction "ECLK30_ECLK30") (pintype "bidirectional"))
      (node (ref "CN101") (pin "B29") (pinfunction "B29_B29") (pintype "bidirectional"))
    )
    (net (code "71") (name "/ECLK90") (class "Default")
      (node (ref "CN100") (pin "ECLK90") (pinfunction "ECLK90_ECLK90") (pintype "bidirectional"))
      (node (ref "CN101") (pin "A31") (pinfunction "A31_A31") (pintype "bidirectional"))
    )
    (net (code "72") (name "/ECLK90A") (class "Default")
      (node (ref "CN100") (pin "ECLK90A") (pinfunction "ECLK90A_ECLK90A") (pintype "bidirectional"))
      (node (ref "CN101") (pin "B30") (pinfunction "B30_B30") (pintype "bidirectional"))
    )
    (net (code "73") (name "/ECPUCLKA") (class "Default")
      (node (ref "CN100") (pin "ECPUCLKA") (pinfunction "ECPUCLKA_ECPUCLKA") (pintype "bidirectional"))
      (node (ref "CN101") (pin "B32") (pinfunction "B32_B32") (pintype "bidirectional"))
    )
    (net (code "74") (name "/EXT90") (class "Default")
      (node (ref "CN100") (pin "EXT90") (pinfunction "EXT90_EXT90") (pintype "bidirectional"))
      (node (ref "CN101") (pin "A3") (pinfunction "A3_A3") (pintype "bidirectional"))
    )
    (net (code "75") (name "/EXTCPU") (class "Default")
      (node (ref "CN100") (pin "EXTCPU") (pinfunction "EXTCPU_EXTCPU") (pintype "bidirectional"))
      (node (ref "CN101") (pin "A43") (pinfunction "A43_A43") (pintype "bidirectional"))
    )
    (net (code "76") (name "/FC0") (class "Default")
      (node (ref "CN100") (pin "FC0") (pinfunction "FC0_FC0") (pintype "bidirectional"))
      (node (ref "CN101") (pin "B7") (pinfunction "B7_B7") (pintype "bidirectional"))
      (node (ref "U100") (pin "FC0") (pinfunction "FC0_FC0") (pintype "bidirectional"))
    )
    (net (code "77") (name "/FC1") (class "Default")
      (node (ref "CN100") (pin "FC1") (pinfunction "FC1_FC1") (pintype "bidirectional"))
      (node (ref "CN101") (pin "B6") (pinfunction "B6_B6") (pintype "bidirectional"))
      (node (ref "U100") (pin "FC1") (pinfunction "FC1_FC1") (pintype "bidirectional"))
    )
    (net (code "78") (name "/FC2") (class "Default")
      (node (ref "CN100") (pin "FC2") (pinfunction "FC2_FC2") (pintype "bidirectional"))
      (node (ref "CN101") (pin "B47") (pinfunction "B47_B47") (pintype "bidirectional"))
      (node (ref "U100") (pin "FC2") (pinfunction "FC2_FC2") (pintype "bidirectional"))
    )
    (net (code "79") (name "/FPUCLK") (class "Default")
      (node (ref "FPUCLK") (pin "2") (pinfunction "2_2") (pintype "passive"))
      (node (ref "U201") (pin "CLK") (pinfunction "CLK_CLK") (pintype "bidirectional"))
    )
    (net (code "80") (name "/R_W") (class "Default")
      (node (ref "CN100") (pin "R_W") (pinfunction "R_W_R_W") (pintype "bidirectional"))
      (node (ref "CN101") (pin "A1") (pinfunction "A1_A1") (pintype "bidirectional"))
      (node (ref "U100") (pin "R_W") (pinfunction "R_W_R_W") (pintype "bidirectional"))
      (node (ref "U201") (pin "R_W") (pinfunction "R_W_R_W") (pintype "bidirectional"))
    )
    (net (code "81") (name "/SIZ0") (class "Default")
      (node (ref "CN100") (pin "SIZ0") (pinfunction "SIZ0_SIZ0") (pintype "bidirectional"))
      (node (ref "CN101") (pin "A46") (pinfunction "A46_A46") (pintype "bidirectional"))
      (node (ref "U100") (pin "SIZ0") (pinfunction "SIZ0_SIZ0") (pintype "bidirectional"))
    )
    (net (code "82") (name "/SIZ1") (class "Default")
      (node (ref "CN100") (pin "SIZ1") (pinfunction "SIZ1_SIZ1") (pintype "bidirectional"))
      (node (ref "CN101") (pin "A49") (pinfunction "A49_A49") (pintype "bidirectional"))
      (node (ref "U100") (pin "SIZ1") (pinfunction "SIZ1_SIZ1") (pintype "bidirectional"))
    )
    (net (code "83") (name "/_AS") (class "Default")
      (node (ref "CN100") (pin "_AS") (pinfunction "_AS__AS") (pintype "bidirectional"))
      (node (ref "CN101") (pin "B55") (pinfunction "B55_B55") (pintype "bidirectional"))
      (node (ref "U100") (pin "_AS") (pinfunction "_AS__AS") (pintype "bidirectional"))
      (node (ref "U201") (pin "_AS") (pinfunction "_AS__AS") (pintype "bidirectional"))
    )
    (net (code "84") (name "/_AVEC") (class "Default")
      (node (ref "CN100") (pin "_AVEC") (pinfunction "_AVEC__AVEC") (pintype "bidirectional"))
      (node (ref "CN101") (pin "B2") (pinfunction "B2_B2") (pintype "bidirectional"))
      (node (ref "U100") (pin "_AVEC") (pinfunction "_AVEC__AVEC") (pintype "bidirectional"))
    )
    (net (code "85") (name "/_BERR") (class "Default")
      (node (ref "CN100") (pin "_BERR") (pinfunction "_BERR__BERR") (pintype "bidirectional"))
      (node (ref "CN101") (pin "A35") (pinfunction "A35_A35") (pintype "bidirectional"))
      (node (ref "U100") (pin "_BERR") (pinfunction "_BERR__BERR") (pintype "bidirectional"))
    )
    (net (code "86") (name "/_BG") (class "Default")
      (node (ref "CN100") (pin "_BG") (pinfunction "_BG__BG") (pintype "bidirectional"))
      (node (ref "CN101") (pin "B31") (pinfunction "B31_B31") (pintype "bidirectional"))
      (node (ref "U100") (pin "_BG") (pinfunction "_BG__BG") (pintype "bidirectional"))
    )
    (net (code "87") (name "/_BG30") (class "Default")
      (node (ref "CN100") (pin "_BG30") (pinfunction "_BG30__BG30") (pintype "bidirectional"))
      (node (ref "CN101") (pin "A57") (pinfunction "A57_A57") (pintype "bidirectional"))
    )
    (net (code "88") (name "/_BGACK") (class "Default")
      (node (ref "CN100") (pin "_BGACK") (pinfunction "_BGACK__BGACK") (pintype "bidirectional"))
      (node (ref "CN101") (pin "A7") (pinfunction "A7_A7") (pintype "bidirectional"))
      (node (ref "U100") (pin "_BGACK") (pinfunction "_BGACK__BGACK") (pintype "bidirectional"))
    )
    (net (code "89") (name "/_BOSS") (class "Default")
      (node (ref "CN100") (pin "_BOSS") (pinfunction "_BOSS__BOSS") (pintype "bidirectional"))
      (node (ref "CN101") (pin "A6") (pinfunction "A6_A6") (pintype "bidirectional"))
      (node (ref "R100") (pin "1") (pinfunction "1_1") (pintype "passive"))
    )
    (net (code "90") (name "/_BR") (class "Default")
      (node (ref "CN100") (pin "_BR") (pinfunction "_BR__BR") (pintype "bidirectional"))
      (node (ref "CN101") (pin "A5") (pinfunction "A5_A5") (pintype "bidirectional"))
      (node (ref "U100") (pin "_BR") (pinfunction "_BR__BR") (pintype "bidirectional"))
    )
    (net (code "91") (name "/_CBACK") (class "Default")
      (node (ref "CN100") (pin "_CBACK") (pinfunction "_CBACK__CBACK") (pintype "bidirectional"))
      (node (ref "CN101") (pin "B42") (pinfunction "B42_B42") (pintype "bidirectional"))
      (node (ref "U100") (pin "_CBACK") (pinfunction "_CBACK__CBACK") (pintype "bidirectional"))
    )
    (net (code "92") (name "/_CBR") (class "Default")
      (node (ref "CN100") (pin "_CBR") (pinfunction "_CBR__CBR") (pintype "bidirectional"))
      (node (ref "CN101") (pin "B56") (pinfunction "B56_B56") (pintype "bidirectional"))
    )
    (net (code "93") (name "/_CBREQ") (class "Default")
      (node (ref "CN100") (pin "_CBREQ") (pinfunction "_CBREQ__CBREQ") (pintype "bidirectional"))
      (node (ref "CN101") (pin "B3") (pinfunction "B3_B3") (pintype "bidirectional"))
      (node (ref "U100") (pin "_CBREQ") (pinfunction "_CBREQ__CBREQ") (pintype "bidirectional"))
    )
    (net (code "94") (name "/_CIIN") (class "Default")
      (node (ref "CN100") (pin "_CIIN") (pinfunction "_CIIN__CIIN") (pintype "bidirectional"))
      (node (ref "CN101") (pin "B43") (pinfunction "B43_B43") (pintype "bidirectional"))
      (node (ref "U100") (pin "_CIIN") (pinfunction "_CIIN__CIIN") (pintype "bidirectional"))
    )
    (net (code "95") (name "/_CIOUT") (class "Default")
      (node (ref "CN100") (pin "_CIOUT") (pinfunction "_CIOUT__CIOUT") (pintype "bidirectional"))
      (node (ref "CN101") (pin "B28") (pinfunction "B28_B28") (pintype "bidirectional"))
      (node (ref "U100") (pin "_CIOUT") (pinfunction "_CIOUT__CIOUT") (pintype "bidirectional"))
    )
    (net (code "96") (name "/_CPURST") (class "Default")
      (node (ref "CN100") (pin "_CPURST") (pinfunction "_CPURST__CPURST") (pintype "bidirectional"))
      (node (ref "CN101") (pin "A33") (pinfunction "A33_A33") (pintype "bidirectional"))
      (node (ref "U100") (pin "_RESET") (pinfunction "_RESET__RESET") (pintype "bidirectional"))
    )
    (net (code "97") (name "/_DBEN") (class "Default")
      (node (ref "CN100") (pin "_DBEN") (pinfunction "_DBEN__DBEN") (pintype "bidirectional"))
      (node (ref "CN101") (pin "A29") (pinfunction "A29_A29") (pintype "bidirectional"))
    )
    (net (code "98") (name "/_DMAEN") (class "Default")
      (node (ref "CN100") (pin "_DMAEN") (pinfunction "_DMAEN__DMAEN") (pintype "bidirectional"))
      (node (ref "CN101") (pin "A39") (pinfunction "A39_A39") (pintype "bidirectional"))
    )
    (net (code "99") (name "/_DS") (class "Default")
      (node (ref "CN100") (pin "_DS") (pinfunction "_DS__DS") (pintype "bidirectional"))
      (node (ref "CN101") (pin "B38") (pinfunction "B38_B38") (pintype "bidirectional"))
      (node (ref "U100") (pin "_DS") (pinfunction "_DS__DS") (pintype "bidirectional"))
      (node (ref "U201") (pin "_DS") (pinfunction "_DS__DS") (pintype "bidirectional"))
    )
    (net (code "100") (name "/_DSACK0") (class "Default")
      (node (ref "CN100") (pin "_DSACK0") (pinfunction "_DSACK0__DSACK0") (pintype "bidirectional"))
      (node (ref "CN101") (pin "A41") (pinfunction "A41_A41") (pintype "bidirectional"))
      (node (ref "U100") (pin "_DSACK0") (pinfunction "_DSACK0__DSACK0") (pintype "bidirectional"))
      (node (ref "U201") (pin "_DSACK0") (pinfunction "_DSACK0__DSACK0") (pintype "bidirectional"))
    )
    (net (code "101") (name "/_DSACK1") (class "Default")
      (node (ref "CN100") (pin "_DSACK1") (pinfunction "_DSACK1__DSACK1") (pintype "bidirectional"))
      (node (ref "CN101") (pin "A2") (pinfunction "A2_A2") (pintype "bidirectional"))
      (node (ref "U100") (pin "_DSACK1") (pinfunction "_DSACK1__DSACK1") (pintype "bidirectional"))
      (node (ref "U201") (pin "_DSACK1") (pinfunction "_DSACK1__DSACK1") (pintype "bidirectional"))
    )
    (net (code "102") (name "/_EBCLR") (class "Default")
      (node (ref "CN100") (pin "_EBCLR") (pinfunction "_EBCLR__EBCLR") (pintype "bidirectional"))
      (node (ref "CN101") (pin "B40") (pinfunction "B40_B40") (pintype "bidirectional"))
    )
    (net (code "103") (name "/_ECS") (class "Default")
      (node (ref "CN100") (pin "_ECS") (pinfunction "_ECS__ECS") (pintype "bidirectional"))
      (node (ref "CN101") (pin "B39") (pinfunction "B39_B39") (pintype "bidirectional"))
    )
    (net (code "104") (name "/_EMUL") (class "Default")
      (node (ref "CN100") (pin "_EMUL") (pinfunction "_EMUL__EMUL") (pintype "bidirectional"))
      (node (ref "CN101") (pin "A36") (pinfunction "A36_A36") (pintype "bidirectional"))
      (node (ref "MMUSEL") (pin "1") (pinfunction "1_1") (pintype "passive"))
      (node (ref "U100") (pin "_CDIS") (pinfunction "_CDIS__CDIS") (pintype "bidirectional"))
    )
    (net (code "105") (name "/_FPUCS") (class "Default")
      (node (ref "CN100") (pin "_FPUCS") (pinfunction "_FPUCS__FPUCS") (pintype "bidirectional"))
      (node (ref "CN101") (pin "B46") (pinfunction "B46_B46") (pintype "bidirectional"))
      (node (ref "R200") (pin "2") (pinfunction "2_2") (pintype "passive"))
      (node (ref "U201") (pin "_CS") (pinfunction "_CS__CS") (pintype "bidirectional"))
    )
    (net (code "106") (name "/_FPURST") (class "Default")
      (node (ref "CN100") (pin "_FPURST") (pinfunction "_FPURST__FPURST") (pintype "bidirectional"))
      (node (ref "CN101") (pin "B37") (pinfunction "B37_B37") (pintype "bidirectional"))
      (node (ref "U201") (pin "_RESET") (pinfunction "_RESET__RESET") (pintype "bidirectional"))
    )
    (net (code "107") (name "/_FPUSIZE") (class "Default")
      (node (ref "R101") (pin "2") (pinfunction "2_2") (pintype "passive"))
      (node (ref "U201") (pin "A0") (pinfunction "A0_A0") (pintype "bidirectional"))
      (node (ref "U201") (pin "SIZE") (pinfunction "_SIZE_SIZE") (pintype "bidirectional"))
    )
    (net (code "108") (name "/_HLT") (class "Default")
      (node (ref "CN100") (pin "_HLT") (pinfunction "_HLT__HLT") (pintype "bidirectional"))
      (node (ref "CN101") (pin "B5") (pinfunction "B5_B5") (pintype "bidirectional"))
      (node (ref "U100") (pin "_HALT") (pinfunction "_HALT__HALT") (pintype "bidirectional"))
    )
    (net (code "109") (name "/_INT2") (class "Default")
      (node (ref "CN100") (pin "_INT2") (pinfunction "_INT2__INT2") (pintype "bidirectional"))
      (node (ref "CN101") (pin "B35") (pinfunction "B35_B35") (pintype "bidirectional"))
    )
    (net (code "110") (name "/_INT6") (class "Default")
      (node (ref "CN100") (pin "_INT6") (pinfunction "_INT6__INT6") (pintype "bidirectional"))
      (node (ref "CN101") (pin "A37") (pinfunction "A37_A37") (pintype "bidirectional"))
    )
    (net (code "111") (name "/_IPEND") (class "Default")
      (node (ref "CN100") (pin "_IPEND") (pinfunction "_IPEND__IPEND") (pintype "bidirectional"))
      (node (ref "CN101") (pin "A44") (pinfunction "A44_A44") (pintype "bidirectional"))
      (node (ref "U100") (pin "_IPEND") (pinfunction "_IPEND__IPEND") (pintype "bidirectional"))
    )
    (net (code "112") (name "/_IPL0") (class "Default")
      (node (ref "CN100") (pin "_IPL0") (pinfunction "IPL0__IPL0") (pintype "bidirectional"))
      (node (ref "CN101") (pin "B45") (pinfunction "B45_B45") (pintype "bidirectional"))
      (node (ref "D1") (pin "A") (pinfunction "A_A") (pintype "passive"))
      (node (ref "U100") (pin "_IPL0") (pinfunction "_IPL0__IPL0") (pintype "bidirectional"))
    )
    (net (code "113") (name "/_IPL1") (class "Default")
      (node (ref "CN100") (pin "_IPL1") (pinfunction "IPL1__IPL1") (pintype "bidirectional"))
      (node (ref "CN101") (pin "B44") (pinfunction "B44_B44") (pintype "bidirectional"))
      (node (ref "D2") (pin "A") (pinfunction "A_A") (pintype "passive"))
      (node (ref "U100") (pin "_IPL1") (pinfunction "_IPL1__IPL1") (pintype "bidirectional"))
    )
    (net (code "114") (name "/_IPL2") (class "Default")
      (node (ref "CN100") (pin "_IPL2") (pinfunction "IPL2__IPL2") (pintype "bidirectional"))
      (node (ref "CN101") (pin "A47") (pinfunction "A47_A47") (pintype "bidirectional"))
      (node (ref "D3") (pin "A") (pinfunction "A_A") (pintype "passive"))
      (node (ref "U100") (pin "_IPL2") (pinfunction "_IPL2__IPL2") (pintype "bidirectional"))
    )
    (net (code "115") (name "/_MMUDIS") (class "Default")
      (node (ref "MMUSEL") (pin "2") (pinfunction "2_2") (pintype "passive"))
      (node (ref "U100") (pin "_MMUDIS") (pinfunction "_MMUDIS__MMUDIS") (pintype "bidirectional"))
    )
    (net (code "116") (name "/_MMUMANUAL") (class "Default")
      (node (ref "MMUMANUAL") (pin "2") (pinfunction "2_2") (pintype "passive"))
      (node (ref "MMUSEL") (pin "3") (pinfunction "3_3") (pintype "passive"))
    )
    (net (code "117") (name "/_OCS") (class "Default")
      (node (ref "CN100") (pin "_OCS") (pinfunction "_OCS__OCS") (pintype "bidirectional"))
      (node (ref "CN101") (pin "A55") (pinfunction "A55_A55") (pintype "bidirectional"))
    )
    (net (code "118") (name "/_PI2C+") (class "Default")
      (node (ref "CN100") (pin "_PI2C+") (pinfunction "_PI2C+__PI2C+") (pintype "bidirectional"))
      (node (ref "CN101") (pin "A40") (pinfunction "A40_A40") (pintype "bidirectional"))
    )
    (net (code "119") (name "/_PLSTERM") (class "Default")
      (node (ref "CN100") (pin "_PLSTERM") (pinfunction "_STERM__PLSTERM") (pintype "bidirectional"))
      (node (ref "CN101") (pin "B1") (pinfunction "B1_B1") (pintype "bidirectional"))
      (node (ref "U100") (pin "_STERM") (pinfunction "_STERM__STERM") (pintype "bidirectional"))
    )
    (net (code "120") (name "/_RAMSLOT") (class "Default")
      (node (ref "CN100") (pin "_RAMSLOT") (pinfunction "_RAMSLOT__RAMSLOT") (pintype "bidirectional"))
      (node (ref "CN101") (pin "B4") (pinfunction "B4_B4") (pintype "bidirectional"))
    )
    (net (code "121") (name "/_RESET") (class "Default")
      (node (ref "CN100") (pin "_RESET") (pinfunction "_RESET__RESET") (pintype "bidirectional"))
      (node (ref "CN101") (pin "A45") (pinfunction "A45_A45") (pintype "bidirectional"))
    )
    (net (code "122") (name "/_RMC") (class "Default")
      (node (ref "CN100") (pin "_RMC") (pinfunction "_RMC__RMC") (pintype "bidirectional"))
      (node (ref "CN101") (pin "A28") (pinfunction "A28_A28") (pintype "bidirectional"))
      (node (ref "U100") (pin "_RMC") (pinfunction "_RMC__RMC") (pintype "bidirectional"))
    )
    (net (code "123") (name "/_SBR") (class "Default")
      (node (ref "CN100") (pin "_SBR") (pinfunction "_SBR__SBR") (pintype "bidirectional"))
      (node (ref "CN101") (pin "A4") (pinfunction "A4_A4") (pintype "bidirectional"))
    )
    (net (code "124") (name "/_SCSI") (class "Default")
      (node (ref "CN100") (pin "_SCSI") (pinfunction "_SCSI__SCSI") (pintype "bidirectional"))
      (node (ref "CN101") (pin "B33") (pinfunction "B33_B33") (pintype "bidirectional"))
    )
    (net (code "125") (name "/_SENSEZ3P+") (class "Default")
      (node (ref "CN100") (pin "_SENSEZ3P+") (pinfunction "_SENSEZ3P+__SENSEZ3P+") (pintype "bidirectional"))
      (node (ref "CN101") (pin "B36") (pinfunction "B36_B36") (pintype "bidirectional"))
    )
    (net (code "126") (name "/_WAIT") (class "Default")
      (node (ref "CN100") (pin "_WAIT") (pinfunction "_WAIT__WAIT") (pintype "bidirectional"))
      (node (ref "CN101") (pin "A38") (pinfunction "A38_A38") (pintype "bidirectional"))
    )
    (net (code "127") (name "GND") (class "Default")
      (node (ref "C100A") (pin "2") (pinfunction "2_2") (pintype "passive"))
      (node (ref "C100B") (pin "2") (pinfunction "2_2") (pintype "passive"))
      (node (ref "C100C") (pin "-") (pinfunction "2_-") (pintype "passive"))
      (node (ref "C100D") (pin "-") (pinfunction "2_-") (pintype "passive"))
      (node (ref "C201A") (pin "1") (pinfunction "1_1") (pintype "passive"))
      (node (ref "C201B") (pin "1") (pinfunction "1_1") (pintype "passive"))
      (node (ref "C201C") (pin "-") (pinfunction "2_-") (pintype "passive"))
      (node (ref "C202A") (pin "2") (pinfunction "2_2") (pintype "passive"))
      (node (ref "CN100") (pin "GND0") (pinfunction "GND0_GND0") (pintype "bidirectional"))
      (node (ref "CN100") (pin "GND1") (pinfunction "GND1_GND1") (pintype "bidirectional"))
      (node (ref "CN100") (pin "GND10") (pinfunction "GND10_GND10") (pintype "bidirectional"))
      (node (ref "CN100") (pin "GND11") (pinfunction "GND11_GND11") (pintype "bidirectional"))
      (node (ref "CN100") (pin "GND12") (pinfunction "GND12_GND12") (pintype "bidirectional"))
      (node (ref "CN100") (pin "GND13") (pinfunction "GND13_GND13") (pintype "bidirectional"))
      (node (ref "CN100") (pin "GND14") (pinfunction "GND14_GND14") (pintype "bidirectional"))
      (node (ref "CN100") (pin "GND15") (pinfunction "GND15_GND15") (pintype "bidirectional"))
      (node (ref "CN100") (pin "GND16") (pinfunction "GND16_GND16") (pintype "bidirectional"))
      (node (ref "CN100") (pin "GND17") (pinfunction "GND17_GND17") (pintype "bidirectional"))
      (node (ref "CN100") (pin "GND18") (pinfunction "GND18_GND18") (pintype "bidirectional"))
      (node (ref "CN100") (pin "GND19") (pinfunction "GND19_GND19") (pintype "bidirectional"))
      (node (ref "CN100") (pin "GND2") (pinfunction "GND2_GND2") (pintype "bidirectional"))
      (node (ref "CN100") (pin "GND20") (pinfunction "GND20_GND20") (pintype "bidirectional"))
      (node (ref "CN100") (pin "GND21") (pinfunction "GND21_GND21") (pintype "bidirectional"))
      (node (ref "CN100") (pin "GND22") (pinfunction "GND22_GND22") (pintype "bidirectional"))
      (node (ref "CN100") (pin "GND23") (pinfunction "GND23_GND23") (pintype "bidirectional"))
      (node (ref "CN100") (pin "GND24") (pinfunction "GND24_GND24") (pintype "bidirectional"))
      (node (ref "CN100") (pin "GND25") (pinfunction "GND25_GND25") (pintype "bidirectional"))
      (node (ref "CN100") (pin "GND26") (pinfunction "GND26_GND26") (pintype "bidirectional"))
      (node (ref "CN100") (pin "GND27") (pinfunction "GND27_GND27") (pintype "bidirectional"))
      (node (ref "CN100") (pin "GND28") (pinfunction "GND28_GND28") (pintype "bidirectional"))
      (node (ref "CN100") (pin "GND29") (pinfunction "GND29_GND29") (pintype "bidirectional"))
      (node (ref "CN100") (pin "GND3") (pinfunction "GND3_GND3") (pintype "bidirectional"))
      (node (ref "CN100") (pin "GND30") (pinfunction "GND30_GND30") (pintype "bidirectional"))
      (node (ref "CN100") (pin "GND31") (pinfunction "GND31_GND31") (pintype "bidirectional"))
      (node (ref "CN100") (pin "GND32") (pinfunction "GND32_GND32") (pintype "bidirectional"))
      (node (ref "CN100") (pin "GND33") (pinfunction "GND33_GND33") (pintype "bidirectional"))
      (node (ref "CN100") (pin "GND34") (pinfunction "GND34_GND34") (pintype "bidirectional"))
      (node (ref "CN100") (pin "GND35") (pinfunction "GND35_GND35") (pintype "bidirectional"))
      (node (ref "CN100") (pin "GND36") (pinfunction "GND36_GND36") (pintype "bidirectional"))
      (node (ref "CN100") (pin "GND37") (pinfunction "GND37_GND37") (pintype "bidirectional"))
      (node (ref "CN100") (pin "GND38") (pinfunction "GND38_GND38") (pintype "bidirectional"))
      (node (ref "CN100") (pin "GND39") (pinfunction "GND39_GND39") (pintype "bidirectional"))
      (node (ref "CN100") (pin "GND4") (pinfunction "GND4_GND4") (pintype "bidirectional"))
      (node (ref "CN100") (pin "GND40") (pinfunction "GND40_GND40") (pintype "bidirectional"))
      (node (ref "CN100") (pin "GND41") (pinfunction "GND41_GND41") (pintype "bidirectional"))
      (node (ref "CN100") (pin "GND42") (pinfunction "GND42_GND42") (pintype "bidirectional"))
      (node (ref "CN100") (pin "GND5") (pinfunction "GND5_GND5") (pintype "bidirectional"))
      (node (ref "CN100") (pin "GND6") (pinfunction "GND6_GND6") (pintype "bidirectional"))
      (node (ref "CN100") (pin "GND7") (pinfunction "GND7_GND7") (pintype "bidirectional"))
      (node (ref "CN100") (pin "GND8") (pinfunction "GND8_GND8") (pintype "bidirectional"))
      (node (ref "CN100") (pin "GND9") (pinfunction "GND9_GND9") (pintype "bidirectional"))
      (node (ref "CN101") (pin "B77") (pinfunction "B77_B77") (pintype "bidirectional"))
      (node (ref "CN101") (pin "B78") (pinfunction "B78_B78") (pintype "bidirectional"))
      (node (ref "CN101") (pin "B79") (pinfunction "B79_B79") (pintype "bidirectional"))
      (node (ref "CN101") (pin "B80") (pinfunction "B80_B80") (pintype "bidirectional"))
      (node (ref "CN101") (pin "B81") (pinfunction "B81_B81") (pintype "bidirectional"))
      (node (ref "CN101") (pin "B82") (pinfunction "B82_B82") (pintype "bidirectional"))
      (node (ref "FAN") (pin "2") (pinfunction "2_2") (pintype "passive"))
      (node (ref "MMUMANUAL") (pin "3") (pinfunction "3_3") (pintype "passive"))
      (node (ref "NMI") (pin "1") (pinfunction "1_1") (pintype "passive"))
      (node (ref "R100") (pin "2") (pinfunction "2_2") (pintype "passive"))
      (node (ref "U100") (pin "GND1") (pinfunction "GND1_GND1") (pintype "bidirectional"))
      (node (ref "U100") (pin "GND10") (pinfunction "GND10_GND10") (pintype "bidirectional"))
      (node (ref "U100") (pin "GND11") (pinfunction "GND11_GND11") (pintype "bidirectional"))
      (node (ref "U100") (pin "GND12") (pinfunction "GND12_GND12") (pintype "bidirectional"))
      (node (ref "U100") (pin "GND13") (pinfunction "GND13_GND13") (pintype "bidirectional"))
      (node (ref "U100") (pin "GND14") (pinfunction "GND14_GND14") (pintype "bidirectional"))
      (node (ref "U100") (pin "GND2") (pinfunction "GND2_GND2") (pintype "bidirectional"))
      (node (ref "U100") (pin "GND3") (pinfunction "GND3_GND3") (pintype "bidirectional"))
      (node (ref "U100") (pin "GND4") (pinfunction "GND4_GND4") (pintype "bidirectional"))
      (node (ref "U100") (pin "GND5") (pinfunction "GND5_GND5") (pintype "bidirectional"))
      (node (ref "U100") (pin "GND6") (pinfunction "GND6_GND6") (pintype "bidirectional"))
      (node (ref "U100") (pin "GND7") (pinfunction "GND7_GND7") (pintype "bidirectional"))
      (node (ref "U100") (pin "GND8") (pinfunction "GND8_GND8") (pintype "bidirectional"))
      (node (ref "U100") (pin "GND9") (pinfunction "GND9_GND9") (pintype "bidirectional"))
      (node (ref "U201") (pin "GND1") (pinfunction "GND1_GND1") (pintype "bidirectional"))
      (node (ref "U201") (pin "GND10") (pinfunction "GND10_GND10") (pintype "bidirectional"))
      (node (ref "U201") (pin "GND11") (pinfunction "GND11_GND11") (pintype "bidirectional"))
      (node (ref "U201") (pin "GND12") (pinfunction "GND11_GND12") (pintype "bidirectional"))
      (node (ref "U201") (pin "GND2") (pinfunction "GND2_GND2") (pintype "bidirectional"))
      (node (ref "U201") (pin "GND3") (pinfunction "GND3_GND3") (pintype "bidirectional"))
      (node (ref "U201") (pin "GND4") (pinfunction "GND4_GND4") (pintype "bidirectional"))
      (node (ref "U201") (pin "GND5") (pinfunction "GND5_GND5") (pintype "bidirectional"))
      (node (ref "U201") (pin "GND6") (pinfunction "GND6_GND6") (pintype "bidirectional"))
      (node (ref "U201") (pin "GND7") (pinfunction "GND7_GND7") (pintype "bidirectional"))
      (node (ref "U201") (pin "GND8") (pinfunction "GND8_GND8") (pintype "bidirectional"))
      (node (ref "U201") (pin "GND9") (pinfunction "GND9_GND9") (pintype "bidirectional"))
      (node (ref "U202") (pin "4") (pinfunction "GND_4") (pintype "power_in"))
      (node (ref "U202") (pin "7") (pinfunction "GND_7") (pintype "power_in"))
    )
    (net (code "128") (name "Net-(D1-PadC)") (class "Default")
      (node (ref "D1") (pin "C") (pinfunction "C_C") (pintype "passive"))
      (node (ref "D2") (pin "C") (pinfunction "C_C") (pintype "passive"))
      (node (ref "D3") (pin "C") (pinfunction "C_C") (pintype "passive"))
      (node (ref "NMI") (pin "2") (pinfunction "2_2") (pintype "passive"))
    )
    (net (code "129") (name "Net-(FPUCLK-Pad3)") (class "Default")
      (node (ref "FPUCLK") (pin "3") (pinfunction "3_3") (pintype "passive"))
      (node (ref "U202") (pin "11") (pinfunction "OUT_11") (pintype "output"))
      (node (ref "U202") (pin "8") (pinfunction "OUT_8") (pintype "output"))
    )
    (net (code "130") (name "unconnected-(CN101-PadA9)") (class "Default")
      (node (ref "CN101") (pin "A9") (pinfunction "A9_A9") (pintype "bidirectional"))
    )
    (net (code "131") (name "unconnected-(CN101-PadA10)") (class "Default")
      (node (ref "CN101") (pin "A10") (pinfunction "A10_A10") (pintype "bidirectional"))
    )
    (net (code "132") (name "unconnected-(CN101-PadA11)") (class "Default")
      (node (ref "CN101") (pin "A11") (pinfunction "A11_A11") (pintype "bidirectional"))
    )
    (net (code "133") (name "unconnected-(CN101-PadA30)") (class "Default")
      (node (ref "CN101") (pin "A30") (pinfunction "A30_A30") (pintype "bidirectional"))
    )
    (net (code "134") (name "unconnected-(CN101-PadA32)") (class "Default")
      (node (ref "CN101") (pin "A32") (pinfunction "A32_A32") (pintype "bidirectional"))
    )
    (net (code "135") (name "unconnected-(CN101-PadA34)") (class "Default")
      (node (ref "CN101") (pin "A34") (pinfunction "A34_A34") (pintype "bidirectional"))
    )
    (net (code "136") (name "unconnected-(CN101-PadA42)") (class "Default")
      (node (ref "CN101") (pin "A42") (pinfunction "A42_A42") (pintype "bidirectional"))
    )
    (net (code "137") (name "unconnected-(CN101-PadA48)") (class "Default")
      (node (ref "CN101") (pin "A48") (pinfunction "A48_A48") (pintype "bidirectional"))
    )
    (net (code "138") (name "unconnected-(CN101-PadA50)") (class "Default")
      (node (ref "CN101") (pin "A50") (pinfunction "A50_A50") (pintype "bidirectional"))
    )
    (net (code "139") (name "unconnected-(CN101-PadA51)") (class "Default")
      (node (ref "CN101") (pin "A51") (pinfunction "A51_A51") (pintype "bidirectional"))
    )
    (net (code "140") (name "unconnected-(CN101-PadA52)") (class "Default")
      (node (ref "CN101") (pin "A52") (pinfunction "A52_A52") (pintype "bidirectional"))
    )
    (net (code "141") (name "unconnected-(CN101-PadA53)") (class "Default")
      (node (ref "CN101") (pin "A53") (pinfunction "A53_A53") (pintype "bidirectional"))
    )
    (net (code "142") (name "unconnected-(CN101-PadA54)") (class "Default")
      (node (ref "CN101") (pin "A54") (pinfunction "A54_A54") (pintype "bidirectional"))
    )
    (net (code "143") (name "unconnected-(CN101-PadA56)") (class "Default")
      (node (ref "CN101") (pin "A56") (pinfunction "A56_A56") (pintype "bidirectional"))
    )
    (net (code "144") (name "unconnected-(CN101-PadA58)") (class "Default")
      (node (ref "CN101") (pin "A58") (pinfunction "A58_A58") (pintype "bidirectional"))
    )
    (net (code "145") (name "unconnected-(CN101-PadA75)") (class "Default")
      (node (ref "CN101") (pin "A75") (pinfunction "A75_A75") (pintype "bidirectional"))
    )
    (net (code "146") (name "unconnected-(CN101-PadA76)") (class "Default")
      (node (ref "CN101") (pin "A76") (pinfunction "A76_A76") (pintype "bidirectional"))
    )
    (net (code "147") (name "unconnected-(CN101-PadB8)") (class "Default")
      (node (ref "CN101") (pin "B8") (pinfunction "B8_B8") (pintype "bidirectional"))
    )
    (net (code "148") (name "unconnected-(CN101-PadB9)") (class "Default")
      (node (ref "CN101") (pin "B9") (pinfunction "B9_B9") (pintype "bidirectional"))
    )
    (net (code "149") (name "unconnected-(CN101-PadB10)") (class "Default")
      (node (ref "CN101") (pin "B10") (pinfunction "B10_B10") (pintype "bidirectional"))
    )
    (net (code "150") (name "unconnected-(CN101-PadB11)") (class "Default")
      (node (ref "CN101") (pin "B11") (pinfunction "B11_B11") (pintype "bidirectional"))
    )
    (net (code "151") (name "unconnected-(CN101-PadB48)") (class "Default")
      (node (ref "CN101") (pin "B48") (pinfunction "B48_B48") (pintype "bidirectional"))
    )
    (net (code "152") (name "unconnected-(CN101-PadB49)") (class "Default")
      (node (ref "CN101") (pin "B49") (pinfunction "B49_B49") (pintype "bidirectional"))
    )
    (net (code "153") (name "unconnected-(CN101-PadB50)") (class "Default")
      (node (ref "CN101") (pin "B50") (pinfunction "B50_B50") (pintype "bidirectional"))
    )
    (net (code "154") (name "unconnected-(CN101-PadB51)") (class "Default")
      (node (ref "CN101") (pin "B51") (pinfunction "B51_B51") (pintype "bidirectional"))
    )
    (net (code "155") (name "unconnected-(CN101-PadB52)") (class "Default")
      (node (ref "CN101") (pin "B52") (pinfunction "B52_B52") (pintype "bidirectional"))
    )
    (net (code "156") (name "unconnected-(CN101-PadB53)") (class "Default")
      (node (ref "CN101") (pin "B53") (pinfunction "B53_B53") (pintype "bidirectional"))
    )
    (net (code "157") (name "unconnected-(CN101-PadB57)") (class "Default")
      (node (ref "CN101") (pin "B57") (pinfunction "B57_B57") (pintype "bidirectional"))
    )
    (net (code "158") (name "unconnected-(CN101-PadB58)") (class "Default")
      (node (ref "CN101") (pin "B58") (pinfunction "B58_B58") (pintype "bidirectional"))
    )
    (net (code "159") (name "unconnected-(CN101-PadB75)") (class "Default")
      (node (ref "CN101") (pin "B75") (pinfunction "B75_B75") (pintype "bidirectional"))
    )
    (net (code "160") (name "unconnected-(CN101-PadB76)") (class "Default")
      (node (ref "CN101") (pin "B76") (pinfunction "B76_B76") (pintype "bidirectional"))
    )
    (net (code "161") (name "unconnected-(U100-Pad_DBEN)") (class "Default")
      (node (ref "U100") (pin "_DBEN") (pinfunction "_DBEN__DBEN") (pintype "bidirectional"))
    )
    (net (code "162") (name "unconnected-(U100-Pad_ECS)") (class "Default")
      (node (ref "U100") (pin "_ECS") (pinfunction "_ECS__ECS") (pintype "bidirectional"))
    )
    (net (code "163") (name "unconnected-(U100-Pad_OCS)") (class "Default")
      (node (ref "U100") (pin "_OCS") (pinfunction "_OCS__OCS") (pintype "bidirectional"))
    )
    (net (code "164") (name "unconnected-(U100-Pad_REFILL)") (class "Default")
      (node (ref "U100") (pin "_REFILL") (pinfunction "_REFILL__REFILL") (pintype "bidirectional"))
    )
    (net (code "165") (name "unconnected-(U100-Pad_STATUS)") (class "Default")
      (node (ref "U100") (pin "_STATUS") (pinfunction "_STATUS__STATUS") (pintype "bidirectional"))
    )
    (net (code "166") (name "unconnected-(U201-Pad_SENSE)") (class "Default")
      (node (ref "U201") (pin "_SENSE") (pinfunction "_SENSE__SENSE") (pintype "bidirectional"))
    )
  )
)
